# 1.net
KiCad netlist of a schematic drawn in EasyEDA
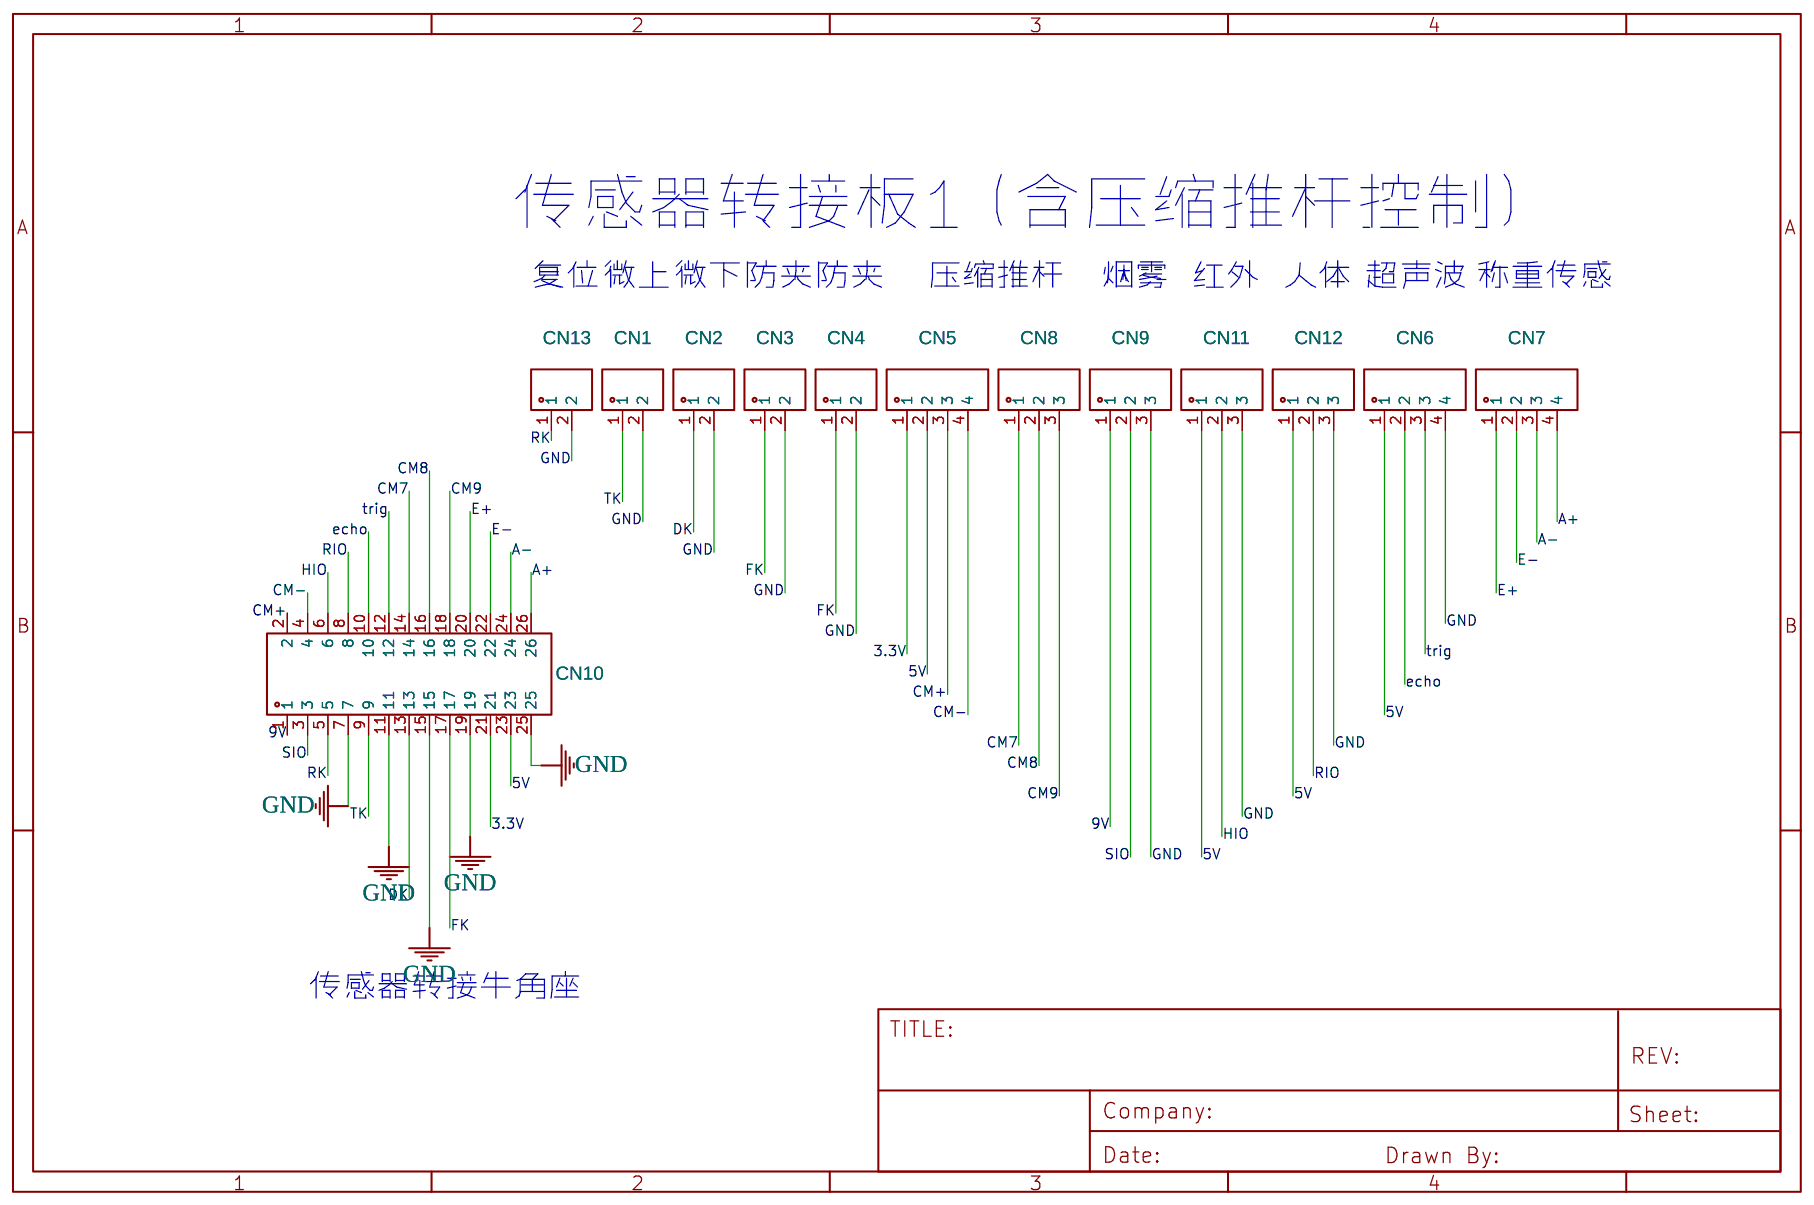
[diagram p0: schematic sheet]

(export (version "E")
  (design (tool "Eeschema 10.0.6"))
  (components
    (comp (ref "CN1")
      (value "KF2EDGR-2.54-2P")
      (fields (field (name "BOM_Supplier Part") "C577594"))
      (libsource (lib "") (part "KF2EDGR-2.54-2P"))
    )
    (comp (ref "CN2")
      (value "KF2EDGR-2.54-2P")
      (fields (field (name "BOM_Supplier Part") "C577594"))
      (libsource (lib "") (part "KF2EDGR-2.54-2P"))
    )
    (comp (ref "CN3")
      (value "KF2EDGR-2.54-2P")
      (fields (field (name "BOM_Supplier Part") "C577594"))
      (libsource (lib "") (part "KF2EDGR-2.54-2P"))
    )
    (comp (ref "CN4")
      (value "KF2EDGR-2.54-2P")
      (fields (field (name "BOM_Supplier Part") "C577594"))
      (libsource (lib "") (part "KF2EDGR-2.54-2P"))
    )
    (comp (ref "CN5")
      (value "KF2EDGR-2.54-4P")
      (fields (field (name "BOM_Supplier Part") "C577596"))
      (libsource (lib "") (part "KF2EDGR-2.54-4P"))
    )
    (comp (ref "CN6")
      (value "KF2EDGR-2.54-4P")
      (fields (field (name "BOM_Supplier Part") "C577596"))
      (libsource (lib "") (part "KF2EDGR-2.54-4P"))
    )
    (comp (ref "CN7")
      (value "KF2EDGR-2.54-4P")
      (fields (field (name "BOM_Supplier Part") "C577596"))
      (libsource (lib "") (part "KF2EDGR-2.54-4P"))
    )
    (comp (ref "CN8")
      (value "KF2EDGR-2.54-3P")
      (fields (field (name "BOM_Supplier Part") "C577595"))
      (libsource (lib "") (part "KF2EDGR-2.54-3P"))
    )
    (comp (ref "CN9")
      (value "KF2EDGR-2.54-3P")
      (fields (field (name "BOM_Supplier Part") "C577595"))
      (libsource (lib "") (part "KF2EDGR-2.54-3P"))
    )
    (comp (ref "CN10")
      (value "Shenzhen")
      (fields
        (field (name "BOM_Manufacturer Part") "B-3000S26P-0110")
        (field (name "BOM_Supplier Part") "C383600")
      )
      (libsource (lib "") (part "B-3000S26P-0110"))
    )
    (comp (ref "CN11")
      (value "KF2EDGR-2.54-3P")
      (fields (field (name "BOM_Supplier Part") "C577595"))
      (libsource (lib "") (part "KF2EDGR-2.54-3P"))
    )
    (comp (ref "CN12")
      (value "KF2EDGR-2.54-3P")
      (fields (field (name "BOM_Supplier Part") "C577595"))
      (libsource (lib "") (part "KF2EDGR-2.54-3P"))
    )
    (comp (ref "CN13")
      (value "KF2EDGR-2.54-2P")
      (fields (field (name "BOM_Supplier Part") "C577594"))
      (libsource (lib "") (part "KF2EDGR-2.54-2P"))
    )
  )
  (nets
    (net (code "1") (name "/3.3V") (class "Default")
      (node (ref "CN10") (pin "21") (pinfunction "21_21") (pintype "unspecified"))
      (node (ref "CN5") (pin "1") (pinfunction "1_1") (pintype "unspecified"))
    )
    (net (code "2") (name "/5V") (class "Default")
      (node (ref "CN10") (pin "23") (pinfunction "23_23") (pintype "unspecified"))
      (node (ref "CN11") (pin "1") (pinfunction "1_1") (pintype "unspecified"))
      (node (ref "CN12") (pin "1") (pinfunction "1_1") (pintype "unspecified"))
      (node (ref "CN5") (pin "2") (pinfunction "2_2") (pintype "unspecified"))
      (node (ref "CN6") (pin "1") (pinfunction "1_1") (pintype "unspecified"))
    )
    (net (code "3") (name "/9V") (class "Default")
      (node (ref "CN10") (pin "1") (pinfunction "1_1") (pintype "unspecified"))
      (node (ref "CN9") (pin "1") (pinfunction "1_1") (pintype "unspecified"))
    )
    (net (code "4") (name "/A+") (class "Default")
      (node (ref "CN10") (pin "26") (pinfunction "26_26") (pintype "unspecified"))
      (node (ref "CN7") (pin "4") (pinfunction "4_4") (pintype "unspecified"))
    )
    (net (code "5") (name "/A-") (class "Default")
      (node (ref "CN10") (pin "24") (pinfunction "24_24") (pintype "unspecified"))
      (node (ref "CN7") (pin "3") (pinfunction "3_3") (pintype "unspecified"))
    )
    (net (code "6") (name "/CM+") (class "Default")
      (node (ref "CN10") (pin "2") (pinfunction "2_2") (pintype "unspecified"))
      (node (ref "CN5") (pin "3") (pinfunction "3_3") (pintype "unspecified"))
    )
    (net (code "7") (name "/CM-") (class "Default")
      (node (ref "CN10") (pin "4") (pinfunction "4_4") (pintype "unspecified"))
      (node (ref "CN5") (pin "4") (pinfunction "4_4") (pintype "unspecified"))
    )
    (net (code "8") (name "/CM7") (class "Default")
      (node (ref "CN10") (pin "14") (pinfunction "14_14") (pintype "unspecified"))
      (node (ref "CN8") (pin "1") (pinfunction "1_1") (pintype "unspecified"))
    )
    (net (code "9") (name "/CM8") (class "Default")
      (node (ref "CN10") (pin "16") (pinfunction "16_16") (pintype "unspecified"))
      (node (ref "CN8") (pin "2") (pinfunction "2_2") (pintype "unspecified"))
    )
    (net (code "10") (name "/CM9") (class "Default")
      (node (ref "CN10") (pin "18") (pinfunction "18_18") (pintype "unspecified"))
      (node (ref "CN8") (pin "3") (pinfunction "3_3") (pintype "unspecified"))
    )
    (net (code "11") (name "/DK") (class "Default")
      (node (ref "CN10") (pin "13") (pinfunction "13_13") (pintype "unspecified"))
      (node (ref "CN2") (pin "1") (pinfunction "1_1") (pintype "unspecified"))
    )
    (net (code "12") (name "/E+") (class "Default")
      (node (ref "CN10") (pin "20") (pinfunction "20_20") (pintype "unspecified"))
      (node (ref "CN7") (pin "1") (pinfunction "1_1") (pintype "unspecified"))
    )
    (net (code "13") (name "/E-") (class "Default")
      (node (ref "CN10") (pin "22") (pinfunction "22_22") (pintype "unspecified"))
      (node (ref "CN7") (pin "2") (pinfunction "2_2") (pintype "unspecified"))
    )
    (net (code "14") (name "/FK") (class "Default")
      (node (ref "CN10") (pin "17") (pinfunction "17_17") (pintype "unspecified"))
      (node (ref "CN3") (pin "1") (pinfunction "1_1") (pintype "unspecified"))
      (node (ref "CN4") (pin "1") (pinfunction "1_1") (pintype "unspecified"))
    )
    (net (code "15") (name "/HIO") (class "Default")
      (node (ref "CN10") (pin "6") (pinfunction "6_6") (pintype "unspecified"))
      (node (ref "CN11") (pin "2") (pinfunction "2_2") (pintype "unspecified"))
    )
    (net (code "16") (name "/RIO") (class "Default")
      (node (ref "CN10") (pin "8") (pinfunction "8_8") (pintype "unspecified"))
      (node (ref "CN12") (pin "2") (pinfunction "2_2") (pintype "unspecified"))
    )
    (net (code "17") (name "/RK") (class "Default")
      (node (ref "CN10") (pin "5") (pinfunction "5_5") (pintype "unspecified"))
      (node (ref "CN13") (pin "1") (pinfunction "1_1") (pintype "unspecified"))
    )
    (net (code "18") (name "/SIO") (class "Default")
      (node (ref "CN10") (pin "3") (pinfunction "3_3") (pintype "unspecified"))
      (node (ref "CN9") (pin "2") (pinfunction "2_2") (pintype "unspecified"))
    )
    (net (code "19") (name "/TK") (class "Default")
      (node (ref "CN1") (pin "1") (pinfunction "1_1") (pintype "unspecified"))
      (node (ref "CN10") (pin "9") (pinfunction "9_9") (pintype "unspecified"))
    )
    (net (code "20") (name "/echo") (class "Default")
      (node (ref "CN10") (pin "10") (pinfunction "10_10") (pintype "unspecified"))
      (node (ref "CN6") (pin "2") (pinfunction "2_2") (pintype "unspecified"))
    )
    (net (code "21") (name "/trig") (class "Default")
      (node (ref "CN10") (pin "12") (pinfunction "12_12") (pintype "unspecified"))
      (node (ref "CN6") (pin "3") (pinfunction "3_3") (pintype "unspecified"))
    )
    (net (code "22") (name "GND") (class "Default")
      (node (ref "CN1") (pin "2") (pinfunction "2_2") (pintype "unspecified"))
      (node (ref "CN10") (pin "11") (pinfunction "11_11") (pintype "unspecified"))
      (node (ref "CN10") (pin "15") (pinfunction "15_15") (pintype "unspecified"))
      (node (ref "CN10") (pin "19") (pinfunction "19_19") (pintype "unspecified"))
      (node (ref "CN10") (pin "25") (pinfunction "25_25") (pintype "unspecified"))
      (node (ref "CN10") (pin "7") (pinfunction "7_7") (pintype "unspecified"))
      (node (ref "CN11") (pin "3") (pinfunction "3_3") (pintype "unspecified"))
      (node (ref "CN12") (pin "3") (pinfunction "3_3") (pintype "unspecified"))
      (node (ref "CN13") (pin "2") (pinfunction "2_2") (pintype "unspecified"))
      (node (ref "CN2") (pin "2") (pinfunction "2_2") (pintype "unspecified"))
      (node (ref "CN3") (pin "2") (pinfunction "2_2") (pintype "unspecified"))
      (node (ref "CN4") (pin "2") (pinfunction "2_2") (pintype "unspecified"))
      (node (ref "CN6") (pin "4") (pinfunction "4_4") (pintype "unspecified"))
      (node (ref "CN9") (pin "3") (pinfunction "3_3") (pintype "unspecified"))
    )
  )
)
